# ST_LINK_V2.net
KiCad netlist of a schematic drawn in Altium Designer
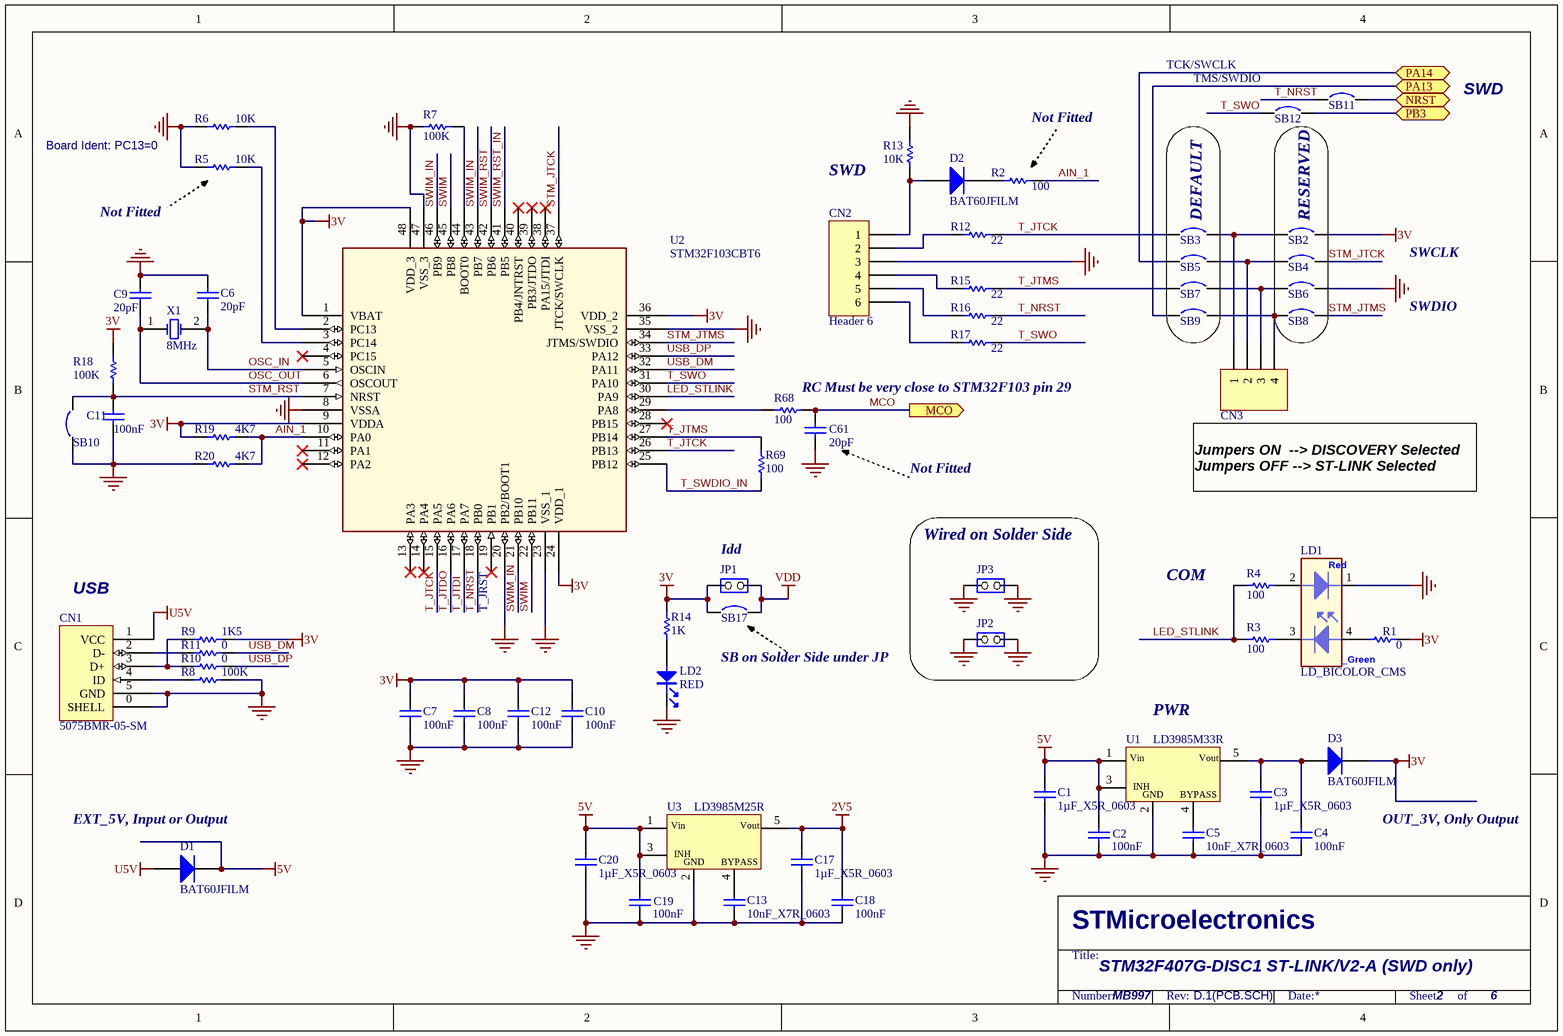
[diagram p0: ST_LINK_V2.SCHDOC]

(export (version "E")
  (design (tool "Eeschema 10.0.6"))
  (components
    (comp (ref "C1")
      (value "1µF_X5R_0603")
      (footprint "0603C")
      (description "0603  X5R 1µF")
      (fields (field (name "TOLERANCE") "10%"))
      (libsource (lib "MB963_1") (part "CAP SMD 0603  X5R 1µF 25V 10%"))
    )
    (comp (ref "C2")
      (value "100nF")
      (footprint "0603C")
      (description "Capacitor")
      (fields (field (name "PUBLISHER") "Altium Limited"))
      (libsource (lib "MB915_1") (part "Cap"))
    )
    (comp (ref "C3")
      (value "1µF_X5R_0603")
      (footprint "0603C")
      (description "0603  X5R 1µF")
      (fields (field (name "TOLERANCE") "10%"))
      (libsource (lib "MB963_1") (part "CAP SMD 0603  X5R 1µF 25V 10%"))
    )
    (comp (ref "C4")
      (value "100nF")
      (footprint "0603C")
      (description "Capacitor")
      (fields (field (name "PUBLISHER") "Altium Limited"))
      (libsource (lib "MB915_1") (part "Cap"))
    )
    (comp (ref "C5")
      (value "10nF_X7R_0603")
      (footprint "0603C")
      (description "0603  X7R 10NF")
      (fields (field (name "TOLERANCE") "10%"))
      (libsource (lib "MB963_1") (part "CAP SMD 0603  X7R 10000PF 50V 10%"))
    )
    (comp (ref "C6")
      (value "20pF")
      (footprint "0402C")
      (description "Capacitor")
      (fields (field (name "PUBLISHER") "Altium Limited"))
      (libsource (lib "MB915_1") (part "Cap"))
    )
    (comp (ref "C7")
      (value "100nF")
      (footprint "0402C")
      (description "Capacitor")
      (fields (field (name "PUBLISHER") "Altium Limited"))
      (libsource (lib "MB915_1") (part "Cap"))
    )
    (comp (ref "C8")
      (value "100nF")
      (footprint "0402C")
      (description "Capacitor")
      (fields (field (name "PUBLISHER") "Altium Limited"))
      (libsource (lib "MB915_1") (part "Cap"))
    )
    (comp (ref "C9")
      (value "20pF")
      (footprint "0402C")
      (description "Capacitor")
      (fields (field (name "PUBLISHER") "Altium Limited"))
      (libsource (lib "MB915_1") (part "Cap"))
    )
    (comp (ref "C10")
      (value "100nF")
      (footprint "0402C")
      (description "Capacitor")
      (fields (field (name "PUBLISHER") "Altium Limited"))
      (libsource (lib "MB915_1") (part "Cap"))
    )
    (comp (ref "C11")
      (value "100nF")
      (footprint "0402C")
      (description "Capacitor")
      (fields (field (name "PUBLISHER") "Altium Limited"))
      (libsource (lib "MB915_1") (part "Cap"))
    )
    (comp (ref "C12")
      (value "100nF")
      (footprint "0402C")
      (description "Capacitor")
      (fields (field (name "PUBLISHER") "Altium Limited"))
      (libsource (lib "MB915_1") (part "Cap"))
    )
    (comp (ref "C13")
      (value "10nF_X7R_0603")
      (footprint "0603C")
      (description "0603  X7R 10NF")
      (fields (field (name "TOLERANCE") "10%"))
      (libsource (lib "MB963_1") (part "CAP SMD 0603  X7R 10000PF 50V 10%"))
    )
    (comp (ref "C17")
      (value "1µF_X5R_0603")
      (footprint "0603C")
      (description "0603  X5R 1µF")
      (fields (field (name "TOLERANCE") "10%"))
      (libsource (lib "MB963_1") (part "CAP SMD 0603  X5R 1µF 25V 10%"))
    )
    (comp (ref "C18")
      (value "100nF")
      (footprint "0603C")
      (description "Capacitor")
      (fields (field (name "PUBLISHER") "Altium Limited"))
      (libsource (lib "MB915_1") (part "Cap"))
    )
    (comp (ref "C19")
      (value "100nF")
      (footprint "0603C")
      (description "Capacitor")
      (fields (field (name "PUBLISHER") "Altium Limited"))
      (libsource (lib "MB915_1") (part "Cap"))
    )
    (comp (ref "C20")
      (value "1µF_X5R_0603")
      (footprint "0603C")
      (description "0603  X5R 1µF")
      (fields (field (name "TOLERANCE") "10%"))
      (libsource (lib "MB963_1") (part "CAP SMD 0603  X5R 1µF 25V 10%"))
    )
    (comp (ref "C61")
      (value "20pF")
      (footprint "0402C")
      (description "Capacitor")
      (fields (field (name "PUBLISHER") "Altium Limited"))
      (libsource (lib "MB915_1") (part "Cap"))
    )
    (comp (ref "CN1")
      (value "5075BMR-05-SM")
      (footprint "USB-MINI-B-SMD")
      (libsource (lib "MB963") (part "USB-MINI-typeB connector"))
    )
    (comp (ref "CN2")
      (value "Header 6")
      (footprint "HDR1X6")
      (description "Header, 6-Pin")
      (fields (field (name "PUBLISHER") "Altium Limited"))
      (libsource (lib "Miscellaneous Connectors") (part "Header 6"))
    )
    (comp (ref "CN3")
      (value "Header 4")
      (footprint "Header 4")
      (description "Header, 4-Pin")
      (fields (field (name "PUBLISHER") "Altium Limited"))
      (libsource (lib "MB963_1") (part "Header 4"))
    )
    (comp (ref "D1")
      (value "BAT60JFILM")
      (footprint "SOD323/A")
      (fields (field (name "PUBLISHER") "Altium Limited"))
      (libsource (lib "MB997") (part "BAT60JFILM"))
    )
    (comp (ref "D2")
      (value "BAT60JFILM")
      (footprint "SOD323/A")
      (fields (field (name "PUBLISHER") "Altium Limited"))
      (libsource (lib "MB997") (part "BAT60JFILM"))
    )
    (comp (ref "D3")
      (value "BAT60JFILM")
      (footprint "SOD323/A")
      (fields (field (name "PUBLISHER") "Altium Limited"))
      (libsource (lib "MB997") (part "BAT60JFILM"))
    )
    (comp (ref "JP1") (value "~") (footprint "SIP2/2.54") (libsource (lib "*") (part "JP2")))
    (comp (ref "JP2") (value "~") (footprint "SIP2/2.54") (libsource (lib "*") (part "JP2")))
    (comp (ref "JP3") (value "~") (footprint "SIP2/2.54") (libsource (lib "*") (part "JP2")))
    (comp (ref "LD1")
      (value "LD_BICOLOR_CMS")
      (footprint "HSMF-A201")
      (description "Bicolor Led")
      (libsource (lib "MB963") (part "LD_BICOLOR_CMS"))
    )
    (comp (ref "LD2") (value "RED") (footprint "0603D") (libsource (lib "MB963_1") (part "PHOTO")))
    (comp (ref "R1")
      (value "0")
      (footprint "0402R")
      (description "Resistor")
      (fields (field (name "PUBLISHER") "Altium Limited"))
      (libsource (lib "MB915_1") (part "res1"))
    )
    (comp (ref "R2")
      (value "100")
      (footprint "0402R")
      (description "Resistor")
      (fields (field (name "PUBLISHER") "Altium Limited"))
      (libsource (lib "MB915_1") (part "res1"))
    )
    (comp (ref "R3")
      (value "100")
      (footprint "0402R")
      (description "Resistor")
      (fields (field (name "PUBLISHER") "Altium Limited"))
      (libsource (lib "MB915_1") (part "res1"))
    )
    (comp (ref "R4")
      (value "100")
      (footprint "0402R")
      (description "Resistor")
      (fields (field (name "PUBLISHER") "Altium Limited"))
      (libsource (lib "MB915_1") (part "res1"))
    )
    (comp (ref "R5")
      (value "10K")
      (footprint "0402R")
      (description "Resistor")
      (fields (field (name "PUBLISHER") "Altium Limited"))
      (libsource (lib "MB915_1") (part "res1"))
    )
    (comp (ref "R6")
      (value "10K")
      (footprint "0402R")
      (description "Resistor")
      (fields (field (name "PUBLISHER") "Altium Limited"))
      (libsource (lib "MB915_1") (part "res1"))
    )
    (comp (ref "R7")
      (value "100K")
      (footprint "0402R")
      (description "Resistor")
      (fields (field (name "PUBLISHER") "Altium Limited"))
      (libsource (lib "MB915_1") (part "res1"))
    )
    (comp (ref "R8")
      (value "100K")
      (footprint "0402R")
      (description "Resistor")
      (fields (field (name "PUBLISHER") "Altium Limited"))
      (libsource (lib "MB915_1") (part "res1"))
    )
    (comp (ref "R9")
      (value "1K5")
      (footprint "0402R")
      (description "Resistor")
      (fields (field (name "PUBLISHER") "Altium Limited"))
      (libsource (lib "MB915_1") (part "res1"))
    )
    (comp (ref "R10")
      (value "0")
      (footprint "0603R")
      (description "Resistor")
      (fields (field (name "PUBLISHER") "Altium Limited"))
      (libsource (lib "MB915_1") (part "res1"))
    )
    (comp (ref "R11")
      (value "0")
      (footprint "0603R")
      (description "Resistor")
      (fields (field (name "PUBLISHER") "Altium Limited"))
      (libsource (lib "MB915_1") (part "res1"))
    )
    (comp (ref "R12")
      (value "22")
      (footprint "0402R")
      (description "Resistor")
      (fields (field (name "PUBLISHER") "Altium Limited"))
      (libsource (lib "MB915_1") (part "res1"))
    )
    (comp (ref "R13")
      (value "10K")
      (footprint "0402R")
      (description "Resistor")
      (fields (field (name "PUBLISHER") "Altium Limited"))
      (libsource (lib "MB915_1") (part "res1"))
    )
    (comp (ref "R14")
      (value "1K")
      (footprint "0402R")
      (description "Resistor")
      (fields (field (name "PUBLISHER") "Altium Limited"))
      (libsource (lib "MB915_1") (part "res1"))
    )
    (comp (ref "R15")
      (value "22")
      (footprint "0402R")
      (description "Resistor")
      (fields (field (name "PUBLISHER") "Altium Limited"))
      (libsource (lib "MB915_1") (part "res1"))
    )
    (comp (ref "R16")
      (value "22")
      (footprint "0402R")
      (description "Resistor")
      (fields (field (name "PUBLISHER") "Altium Limited"))
      (libsource (lib "MB915_1") (part "res1"))
    )
    (comp (ref "R17")
      (value "22")
      (footprint "0402R")
      (description "Resistor")
      (fields (field (name "PUBLISHER") "Altium Limited"))
      (libsource (lib "MB915_1") (part "res1"))
    )
    (comp (ref "R18")
      (value "100K")
      (footprint "0402R")
      (description "Resistor")
      (fields (field (name "PUBLISHER") "Altium Limited"))
      (libsource (lib "MB915_1") (part "res1"))
    )
    (comp (ref "R19")
      (value "4K7")
      (footprint "0402R")
      (description "Resistor")
      (fields (field (name "PUBLISHER") "Altium Limited"))
      (libsource (lib "MB915_1") (part "res1"))
    )
    (comp (ref "R20")
      (value "4K7")
      (footprint "0402R")
      (description "Resistor")
      (fields (field (name "PUBLISHER") "Altium Limited"))
      (libsource (lib "MB915_1") (part "res1"))
    )
    (comp (ref "R68")
      (value "100")
      (footprint "0402R")
      (description "Resistor")
      (fields (field (name "PUBLISHER") "Altium Limited"))
      (libsource (lib "MB915_1") (part "res1"))
    )
    (comp (ref "R69")
      (value "100")
      (footprint "0402R")
      (description "Resistor")
      (fields (field (name "PUBLISHER") "Altium Limited"))
      (libsource (lib "MB915_1") (part "res1"))
    )
    (comp (ref "SB2")
      (value "Circuit Breaker")
      (footprint "JP2_SMD")
      (fields (field (name "PUBLISHER") "Altium Limited"))
      (libsource (lib "MB915") (part "Circuit Breaker"))
    )
    (comp (ref "SB3")
      (value "Circuit Breaker")
      (footprint "JP2_SMD")
      (fields (field (name "PUBLISHER") "Altium Limited"))
      (libsource (lib "MB915") (part "Circuit Breaker"))
    )
    (comp (ref "SB4")
      (value "Circuit Breaker")
      (footprint "JP2_SMD")
      (fields (field (name "PUBLISHER") "Altium Limited"))
      (libsource (lib "MB915") (part "Circuit Breaker"))
    )
    (comp (ref "SB5")
      (value "Circuit Breaker")
      (footprint "JP2_SMD")
      (fields (field (name "PUBLISHER") "Altium Limited"))
      (libsource (lib "MB915") (part "Circuit Breaker"))
    )
    (comp (ref "SB6")
      (value "Circuit Breaker")
      (footprint "JP2_SMD")
      (fields (field (name "PUBLISHER") "Altium Limited"))
      (libsource (lib "MB915") (part "Circuit Breaker"))
    )
    (comp (ref "SB7")
      (value "Circuit Breaker")
      (footprint "JP2_SMD")
      (fields (field (name "PUBLISHER") "Altium Limited"))
      (libsource (lib "MB915") (part "Circuit Breaker"))
    )
    (comp (ref "SB8")
      (value "Circuit Breaker")
      (footprint "JP2_SMD")
      (fields (field (name "PUBLISHER") "Altium Limited"))
      (libsource (lib "MB915") (part "Circuit Breaker"))
    )
    (comp (ref "SB9")
      (value "Circuit Breaker")
      (footprint "JP2_SMD")
      (fields (field (name "PUBLISHER") "Altium Limited"))
      (libsource (lib "MB915") (part "Circuit Breaker"))
    )
    (comp (ref "SB10")
      (value "Circuit Breaker")
      (footprint "JP2_SMD")
      (fields (field (name "PUBLISHER") "Altium Limited"))
      (libsource (lib "MB915") (part "Circuit Breaker"))
    )
    (comp (ref "SB11")
      (value "Circuit Breaker")
      (footprint "JP2_SMD")
      (fields (field (name "PUBLISHER") "Altium Limited"))
      (libsource (lib "MB915") (part "Circuit Breaker"))
    )
    (comp (ref "SB12")
      (value "Circuit Breaker")
      (footprint "JP2_SMD")
      (fields (field (name "PUBLISHER") "Altium Limited"))
      (libsource (lib "MB915") (part "Circuit Breaker"))
    )
    (comp (ref "SB17")
      (value "Circuit Breaker")
      (footprint "JP2_SMD")
      (fields (field (name "PUBLISHER") "Altium Limited"))
      (libsource (lib "MB915") (part "Circuit Breaker"))
    )
    (comp (ref "U1")
      (value "LD3985M33R")
      (footprint "SOT-23-5L")
      (description "Ultra low drop-low noise BiCMOS voltage, regulators low ESR capacitors compatible")
      (libsource (lib "MB997") (part "LD3985M33R"))
    )
    (comp (ref "U2")
      (value "STM32F103CBT6")
      (footprint "QFP48 7x7")
      (description "Medium-density performance line ARM-based 32-bit MCU with 128KB Flash")
      (libsource (lib "MCD_TOOLS") (part "STM32F103CBT6"))
    )
    (comp (ref "U3")
      (value "LD3985M25R")
      (footprint "SOT-23-5L")
      (description "Ultra low drop-low noise BiCMOS voltage, regulators low ESR capacitors compatible")
      (libsource (lib "MB997") (part "LD3985M25R"))
    )
    (comp (ref "X1")
      (value "8MHz")
      (footprint "XTAL1")
      (description "Crystal Oscillator")
      (fields (field (name "PUBLISHER") "Altium Limited"))
      (libsource (lib "MB963_1") (part "XTAL"))
    )
  )
  (nets
    (net (code "1") (name "/AIN_1") (class "Default")
      (node (ref "R19") (pin "2") (pinfunction "2_2") (pintype "passive"))
      (node (ref "R2") (pin "2") (pinfunction "2_2") (pintype "passive"))
      (node (ref "R20") (pin "2") (pinfunction "2_2") (pintype "passive"))
      (node (ref "U2") (pin "10") (pinfunction "PA0_10") (pintype "bidirectional"))
    )
    (net (code "2") (name "/LED_STLINK") (class "Default")
      (node (ref "R3") (pin "1") (pinfunction "1_1") (pintype "passive"))
      (node (ref "R4") (pin "1") (pinfunction "1_1") (pintype "passive"))
      (node (ref "U2") (pin "30") (pinfunction "PA9_30") (pintype "bidirectional"))
    )
    (net (code "3") (name "/MCO") (class "Default")
      (node (ref "C61") (pin "1") (pinfunction "1_1") (pintype "passive"))
      (node (ref "R68") (pin "2") (pinfunction "2_2") (pintype "passive"))
    )
    (net (code "4") (name "/NRST") (class "Default")
      (node (ref "SB11") (pin "2") (pinfunction "2_2") (pintype "passive"))
    )
    (net (code "5") (name "/OSC_IN") (class "Default")
      (node (ref "C6") (pin "2") (pinfunction "2_2") (pintype "passive"))
      (node (ref "U2") (pin "5") (pinfunction "OSCIN_5") (pintype "input"))
      (node (ref "X1") (pin "2") (pinfunction "OSC2_2") (pintype "passive"))
    )
    (net (code "6") (name "/OSC_OUT") (class "Default")
      (node (ref "C9") (pin "2") (pinfunction "2_2") (pintype "passive"))
      (node (ref "U2") (pin "6") (pinfunction "OSCOUT_6") (pintype "output"))
      (node (ref "X1") (pin "1") (pinfunction "OSC1_1") (pintype "passive"))
    )
    (net (code "7") (name "/PA13") (class "Default")
      (node (ref "SB9") (pin "1") (pinfunction "1_1") (pintype "passive"))
    )
    (net (code "8") (name "/PA14") (class "Default")
      (node (ref "SB5") (pin "1") (pinfunction "1_1") (pintype "passive"))
    )
    (net (code "9") (name "/PB3") (class "Default")
      (node (ref "SB12") (pin "2") (pinfunction "2_2") (pintype "passive"))
    )
    (net (code "10") (name "/STM_JTCK") (class "Default")
      (node (ref "SB4") (pin "2") (pinfunction "2_2") (pintype "passive"))
      (node (ref "U2") (pin "37") (pinfunction "JTCK/SWCLK_37") (pintype "bidirectional"))
    )
    (net (code "11") (name "/STM_JTMS") (class "Default")
      (node (ref "SB8") (pin "2") (pinfunction "2_2") (pintype "passive"))
      (node (ref "U2") (pin "34") (pinfunction "JTMS/SWDIO_34") (pintype "bidirectional"))
    )
    (net (code "12") (name "/STM_RST") (class "Default")
      (node (ref "C11") (pin "2") (pinfunction "2_2") (pintype "passive"))
      (node (ref "R18") (pin "1") (pinfunction "1_1") (pintype "passive"))
      (node (ref "SB10") (pin "2") (pinfunction "2_2") (pintype "passive"))
      (node (ref "U2") (pin "7") (pinfunction "NRST_7") (pintype "input"))
    )
    (net (code "13") (name "/SWIM") (class "Default")
      (node (ref "U2") (pin "22") (pinfunction "PB11_22") (pintype "bidirectional"))
      (node (ref "U2") (pin "45") (pinfunction "PB8_45") (pintype "bidirectional"))
    )
    (net (code "14") (name "/SWIM_IN") (class "Default")
      (node (ref "U2") (pin "21") (pinfunction "PB10_21") (pintype "bidirectional"))
      (node (ref "U2") (pin "43") (pinfunction "PB7_43") (pintype "bidirectional"))
      (node (ref "U2") (pin "46") (pinfunction "PB9_46") (pintype "bidirectional"))
    )
    (net (code "15") (name "/SWIM_RST") (class "Default")
      (node (ref "U2") (pin "42") (pinfunction "PB6_42") (pintype "bidirectional"))
    )
    (net (code "16") (name "/SWIM_RST_IN") (class "Default")
      (node (ref "U2") (pin "41") (pinfunction "PB5_41") (pintype "bidirectional"))
    )
    (net (code "17") (name "/T_JTCK") (class "Default")
      (node (ref "R12") (pin "2") (pinfunction "2_2") (pintype "passive"))
      (node (ref "SB3") (pin "1") (pinfunction "1_1") (pintype "passive"))
      (node (ref "U2") (pin "15") (pinfunction "PA5_15") (pintype "bidirectional"))
      (node (ref "U2") (pin "26") (pinfunction "PB13_26") (pintype "bidirectional"))
    )
    (net (code "18") (name "/T_JTDI") (class "Default")
      (node (ref "U2") (pin "17") (pinfunction "PA7_17") (pintype "bidirectional"))
    )
    (net (code "19") (name "/T_JTDO") (class "Default")
      (node (ref "U2") (pin "16") (pinfunction "PA6_16") (pintype "bidirectional"))
    )
    (net (code "20") (name "/T_JTMS") (class "Default")
      (node (ref "R15") (pin "2") (pinfunction "2_2") (pintype "passive"))
      (node (ref "R69") (pin "2") (pinfunction "2_2") (pintype "passive"))
      (node (ref "SB7") (pin "1") (pinfunction "1_1") (pintype "passive"))
      (node (ref "U2") (pin "27") (pinfunction "PB14_27") (pintype "bidirectional"))
    )
    (net (code "21") (name "/T_NRST") (class "Default")
      (node (ref "R16") (pin "2") (pinfunction "2_2") (pintype "passive"))
      (node (ref "SB11") (pin "1") (pinfunction "1_1") (pintype "passive"))
      (node (ref "U2") (pin "18") (pinfunction "PB0_18") (pintype "bidirectional"))
    )
    (net (code "22") (name "/T_SWDIO_IN") (class "Default")
      (node (ref "R69") (pin "1") (pinfunction "1_1") (pintype "passive"))
      (node (ref "U2") (pin "25") (pinfunction "PB12_25") (pintype "bidirectional"))
    )
    (net (code "23") (name "/T_SWO") (class "Default")
      (node (ref "R17") (pin "2") (pinfunction "2_2") (pintype "passive"))
      (node (ref "SB12") (pin "1") (pinfunction "1_1") (pintype "passive"))
      (node (ref "U2") (pin "31") (pinfunction "PA10_31") (pintype "bidirectional"))
    )
    (net (code "24") (name "/USB_DM") (class "Default")
      (node (ref "R11") (pin "2") (pinfunction "2_2") (pintype "passive"))
      (node (ref "U2") (pin "32") (pinfunction "PA11_32") (pintype "bidirectional"))
    )
    (net (code "25") (name "/USB_DP") (class "Default")
      (node (ref "R10") (pin "2") (pinfunction "2_2") (pintype "passive"))
      (node (ref "U2") (pin "33") (pinfunction "PA12_33") (pintype "bidirectional"))
    )
    (net (code "26") (name "2V5") (class "Default")
      (node (ref "C17") (pin "1") (pinfunction "1_1") (pintype "passive"))
      (node (ref "C18") (pin "2") (pinfunction "2_2") (pintype "passive"))
      (node (ref "U3") (pin "5") (pinfunction "Vout_5") (pintype "passive"))
    )
    (net (code "27") (name "3V") (class "Default")
      (node (ref "C10") (pin "2") (pinfunction "2_2") (pintype "passive"))
      (node (ref "C12") (pin "1") (pinfunction "1_1") (pintype "passive"))
      (node (ref "C7") (pin "2") (pinfunction "2_2") (pintype "passive"))
      (node (ref "C8") (pin "2") (pinfunction "2_2") (pintype "passive"))
      (node (ref "D3") (pin "2") (pinfunction "K_2") (pintype "passive"))
      (node (ref "JP1") (pin "1") (pinfunction "COMMON_1") (pintype "passive"))
      (node (ref "R1") (pin "2") (pinfunction "2_2") (pintype "passive"))
      (node (ref "R14") (pin "2") (pinfunction "2_2") (pintype "passive"))
      (node (ref "R18") (pin "2") (pinfunction "2_2") (pintype "passive"))
      (node (ref "R19") (pin "1") (pinfunction "1_1") (pintype "passive"))
      (node (ref "R9") (pin "2") (pinfunction "2_2") (pintype "passive"))
      (node (ref "SB17") (pin "1") (pinfunction "1_1") (pintype "passive"))
      (node (ref "SB2") (pin "2") (pinfunction "2_2") (pintype "passive"))
      (node (ref "U2") (pin "1") (pinfunction "VBAT_1") (pintype "power_in"))
      (node (ref "U2") (pin "24") (pinfunction "VDD_1_24") (pintype "power_in"))
      (node (ref "U2") (pin "36") (pinfunction "VDD_2_36") (pintype "power_in"))
      (node (ref "U2") (pin "48") (pinfunction "VDD_3_48") (pintype "power_in"))
      (node (ref "U2") (pin "9") (pinfunction "VDDA_9") (pintype "power_in"))
    )
    (net (code "28") (name "5V") (class "Default")
      (node (ref "C1") (pin "2") (pinfunction "2_2") (pintype "passive"))
      (node (ref "C19") (pin "2") (pinfunction "2_2") (pintype "passive"))
      (node (ref "C2") (pin "2") (pinfunction "2_2") (pintype "passive"))
      (node (ref "C20") (pin "2") (pinfunction "2_2") (pintype "passive"))
      (node (ref "D1") (pin "2") (pinfunction "K_2") (pintype "passive"))
      (node (ref "U1") (pin "1") (pinfunction "Vin_1") (pintype "passive"))
      (node (ref "U1") (pin "3") (pinfunction "CE_3") (pintype "passive"))
      (node (ref "U3") (pin "1") (pinfunction "Vin_1") (pintype "passive"))
      (node (ref "U3") (pin "3") (pinfunction "CE_3") (pintype "passive"))
    )
    (net (code "29") (name "GND") (class "Default")
      (node (ref "C1") (pin "1") (pinfunction "1_1") (pintype "passive"))
      (node (ref "C10") (pin "1") (pinfunction "1_1") (pintype "passive"))
      (node (ref "C11") (pin "1") (pinfunction "1_1") (pintype "passive"))
      (node (ref "C12") (pin "2") (pinfunction "2_2") (pintype "passive"))
      (node (ref "C13") (pin "1") (pinfunction "1_1") (pintype "passive"))
      (node (ref "C17") (pin "2") (pinfunction "2_2") (pintype "passive"))
      (node (ref "C18") (pin "1") (pinfunction "1_1") (pintype "passive"))
      (node (ref "C19") (pin "1") (pinfunction "1_1") (pintype "passive"))
      (node (ref "C2") (pin "1") (pinfunction "1_1") (pintype "passive"))
      (node (ref "C20") (pin "1") (pinfunction "1_1") (pintype "passive"))
      (node (ref "C3") (pin "2") (pinfunction "2_2") (pintype "passive"))
      (node (ref "C4") (pin "1") (pinfunction "1_1") (pintype "passive"))
      (node (ref "C5") (pin "1") (pinfunction "1_1") (pintype "passive"))
      (node (ref "C6") (pin "1") (pinfunction "1_1") (pintype "passive"))
      (node (ref "C61") (pin "2") (pinfunction "2_2") (pintype "passive"))
      (node (ref "C7") (pin "1") (pinfunction "1_1") (pintype "passive"))
      (node (ref "C8") (pin "1") (pinfunction "1_1") (pintype "passive"))
      (node (ref "C9") (pin "1") (pinfunction "1_1") (pintype "passive"))
      (node (ref "CN1") (pin "0") (pinfunction "SHELL_0") (pintype "power_in"))
      (node (ref "CN1") (pin "5") (pinfunction "GND_5") (pintype "power_in"))
      (node (ref "CN2") (pin "3") (pinfunction "3_3") (pintype "passive"))
      (node (ref "JP2") (pin "1") (pinfunction "COMMON_1") (pintype "passive"))
      (node (ref "JP2") (pin "2") (pinfunction "NO_2") (pintype "passive"))
      (node (ref "JP3") (pin "1") (pinfunction "COMMON_1") (pintype "passive"))
      (node (ref "JP3") (pin "2") (pinfunction "NO_2") (pintype "passive"))
      (node (ref "LD1") (pin "1") (pinfunction "1_1") (pintype "passive"))
      (node (ref "LD2") (pin "2") (pintype "passive"))
      (node (ref "R13") (pin "2") (pinfunction "2_2") (pintype "passive"))
      (node (ref "R20") (pin "1") (pinfunction "1_1") (pintype "passive"))
      (node (ref "R5") (pin "1") (pinfunction "1_1") (pintype "passive"))
      (node (ref "R6") (pin "1") (pinfunction "1_1") (pintype "passive"))
      (node (ref "R7") (pin "1") (pinfunction "1_1") (pintype "passive"))
      (node (ref "R8") (pin "2") (pinfunction "2_2") (pintype "passive"))
      (node (ref "SB10") (pin "1") (pinfunction "1_1") (pintype "passive"))
      (node (ref "SB6") (pin "2") (pinfunction "2_2") (pintype "passive"))
      (node (ref "U1") (pin "2") (pinfunction "GND_2") (pintype "passive"))
      (node (ref "U2") (pin "20") (pinfunction "PB2/BOOT1_20") (pintype "bidirectional"))
      (node (ref "U2") (pin "23") (pinfunction "VSS_1_23") (pintype "power_in"))
      (node (ref "U2") (pin "35") (pinfunction "VSS_2_35") (pintype "power_in"))
      (node (ref "U2") (pin "47") (pinfunction "VSS_3_47") (pintype "power_in"))
      (node (ref "U2") (pin "8") (pinfunction "VSSA_8") (pintype "power_in"))
      (node (ref "U3") (pin "2") (pinfunction "GND_2") (pintype "passive"))
    )
    (net (code "30") (name "Net-(CN1-D+)") (class "Default")
      (node (ref "CN1") (pin "3") (pinfunction "D+_3") (pintype "bidirectional"))
      (node (ref "R10") (pin "1") (pinfunction "1_1") (pintype "passive"))
      (node (ref "R9") (pin "1") (pinfunction "1_1") (pintype "passive"))
    )
    (net (code "31") (name "Net-(CN1-D-)") (class "Default")
      (node (ref "CN1") (pin "2") (pinfunction "D-_2") (pintype "bidirectional"))
      (node (ref "R11") (pin "1") (pinfunction "1_1") (pintype "passive"))
    )
    (net (code "32") (name "Net-(CN1-ID)") (class "Default")
      (node (ref "CN1") (pin "4") (pinfunction "ID_4") (pintype "input"))
      (node (ref "R8") (pin "1") (pinfunction "1_1") (pintype "passive"))
    )
    (net (code "33") (name "Net-(CN2-Pad2)") (class "Default")
      (node (ref "CN2") (pin "2") (pinfunction "2_2") (pintype "passive"))
      (node (ref "R12") (pin "1") (pinfunction "1_1") (pintype "passive"))
    )
    (net (code "34") (name "Net-(CN2-Pad4)") (class "Default")
      (node (ref "CN2") (pin "4") (pinfunction "4_4") (pintype "passive"))
      (node (ref "R15") (pin "1") (pinfunction "1_1") (pintype "passive"))
    )
    (net (code "35") (name "Net-(CN2-Pad5)") (class "Default")
      (node (ref "CN2") (pin "5") (pinfunction "5_5") (pintype "passive"))
      (node (ref "R16") (pin "1") (pinfunction "1_1") (pintype "passive"))
    )
    (net (code "36") (name "Net-(CN2-Pad6)") (class "Default")
      (node (ref "CN2") (pin "6") (pinfunction "6_6") (pintype "passive"))
      (node (ref "R17") (pin "1") (pinfunction "1_1") (pintype "passive"))
    )
    (net (code "37") (name "Net-(CN3-Pad1)") (class "Default")
      (node (ref "CN3") (pin "1") (pinfunction "1_1") (pintype "passive"))
      (node (ref "SB2") (pin "1") (pinfunction "1_1") (pintype "passive"))
      (node (ref "SB3") (pin "2") (pinfunction "2_2") (pintype "passive"))
    )
    (net (code "38") (name "Net-(CN3-Pad2)") (class "Default")
      (node (ref "CN3") (pin "2") (pinfunction "2_2") (pintype "passive"))
      (node (ref "SB4") (pin "1") (pinfunction "1_1") (pintype "passive"))
      (node (ref "SB5") (pin "2") (pinfunction "2_2") (pintype "passive"))
    )
    (net (code "39") (name "Net-(CN3-Pad3)") (class "Default")
      (node (ref "CN3") (pin "3") (pinfunction "3_3") (pintype "passive"))
      (node (ref "SB6") (pin "1") (pinfunction "1_1") (pintype "passive"))
      (node (ref "SB7") (pin "2") (pinfunction "2_2") (pintype "passive"))
    )
    (net (code "40") (name "Net-(CN3-Pad4)") (class "Default")
      (node (ref "CN3") (pin "4") (pinfunction "4_4") (pintype "passive"))
      (node (ref "SB8") (pin "1") (pinfunction "1_1") (pintype "passive"))
      (node (ref "SB9") (pin "2") (pinfunction "2_2") (pintype "passive"))
    )
    (net (code "41") (name "Net-(D2-A)") (class "Default")
      (node (ref "CN2") (pin "1") (pinfunction "1_1") (pintype "passive"))
      (node (ref "D2") (pin "1") (pinfunction "A_1") (pintype "passive"))
      (node (ref "R13") (pin "1") (pinfunction "1_1") (pintype "passive"))
    )
    (net (code "42") (name "Net-(D2-K)") (class "Default")
      (node (ref "D2") (pin "2") (pinfunction "K_2") (pintype "passive"))
      (node (ref "R2") (pin "1") (pinfunction "1_1") (pintype "passive"))
    )
    (net (code "43") (name "Net-(D3-A)") (class "Default")
      (node (ref "C3") (pin "1") (pinfunction "1_1") (pintype "passive"))
      (node (ref "C4") (pin "2") (pinfunction "2_2") (pintype "passive"))
      (node (ref "D3") (pin "1") (pinfunction "A_1") (pintype "passive"))
      (node (ref "U1") (pin "5") (pinfunction "Vout_5") (pintype "passive"))
    )
    (net (code "44") (name "Net-(LD1-Pad2)") (class "Default")
      (node (ref "LD1") (pin "2") (pinfunction "2_2") (pintype "passive"))
      (node (ref "R4") (pin "2") (pinfunction "2_2") (pintype "passive"))
    )
    (net (code "45") (name "Net-(LD1-Pad3)") (class "Default")
      (node (ref "LD1") (pin "3") (pinfunction "3_3") (pintype "passive"))
      (node (ref "R3") (pin "2") (pinfunction "2_2") (pintype "passive"))
    )
    (net (code "46") (name "Net-(LD1-Pad4)") (class "Default")
      (node (ref "LD1") (pin "4") (pinfunction "4_4") (pintype "passive"))
      (node (ref "R1") (pin "1") (pinfunction "1_1") (pintype "passive"))
    )
    (net (code "47") (name "Net-(LD2-Pad1)") (class "Default")
      (node (ref "LD2") (pin "1") (pintype "passive"))
      (node (ref "R14") (pin "1") (pinfunction "1_1") (pintype "passive"))
    )
    (net (code "48") (name "Net-(U1-BYPASS)") (class "Default")
      (node (ref "C5") (pin "2") (pinfunction "2_2") (pintype "passive"))
      (node (ref "U1") (pin "4") (pinfunction "BYPASS_4") (pintype "passive"))
    )
    (net (code "49") (name "Net-(U2-BOOT0)") (class "Default")
      (node (ref "R7") (pin "2") (pinfunction "2_2") (pintype "passive"))
      (node (ref "U2") (pin "44") (pinfunction "BOOT0_44") (pintype "bidirectional"))
    )
    (net (code "50") (name "Net-(U2-PA8)") (class "Default")
      (node (ref "R68") (pin "1") (pinfunction "1_1") (pintype "passive"))
      (node (ref "U2") (pin "29") (pinfunction "PA8_29") (pintype "bidirectional"))
    )
    (net (code "51") (name "Net-(U2-PC13)") (class "Default")
      (node (ref "R6") (pin "2") (pinfunction "2_2") (pintype "passive"))
      (node (ref "U2") (pin "2") (pinfunction "PC13_2") (pintype "bidirectional"))
    )
    (net (code "52") (name "Net-(U2-PC14)") (class "Default")
      (node (ref "R5") (pin "2") (pinfunction "2_2") (pintype "passive"))
      (node (ref "U2") (pin "3") (pinfunction "PC14_3") (pintype "bidirectional"))
    )
    (net (code "53") (name "Net-(U3-BYPASS)") (class "Default")
      (node (ref "C13") (pin "2") (pinfunction "2_2") (pintype "passive"))
      (node (ref "U3") (pin "4") (pinfunction "BYPASS_4") (pintype "passive"))
    )
    (net (code "54") (name "U5V") (class "Default")
      (node (ref "CN1") (pin "1") (pinfunction "VCC_1") (pintype "power_in"))
      (node (ref "D1") (pin "1") (pinfunction "A_1") (pintype "passive"))
    )
    (net (code "55") (name "VDD") (class "Default")
      (node (ref "JP1") (pin "2") (pinfunction "NO_2") (pintype "passive"))
      (node (ref "SB17") (pin "2") (pinfunction "2_2") (pintype "passive"))
    )
    (net (code "56") (name "unconnected-(U2-PA1-Pad11)") (class "Default")
      (node (ref "U2") (pin "11") (pinfunction "PA1_11") (pintype "bidirectional+no_connect"))
    )
    (net (code "57") (name "unconnected-(U2-PA2-Pad12)") (class "Default")
      (node (ref "U2") (pin "12") (pinfunction "PA2_12") (pintype "bidirectional+no_connect"))
    )
    (net (code "58") (name "unconnected-(U2-PA3-Pad13)") (class "Default")
      (node (ref "U2") (pin "13") (pinfunction "PA3_13") (pintype "bidirectional+no_connect"))
    )
    (net (code "59") (name "unconnected-(U2-PA4-Pad14)") (class "Default")
      (node (ref "U2") (pin "14") (pinfunction "PA4_14") (pintype "bidirectional+no_connect"))
    )
    (net (code "60") (name "unconnected-(U2-PA15{slash}JTDI-Pad38)") (class "Default")
      (node (ref "U2") (pin "38") (pinfunction "PA15/JTDI_38") (pintype "bidirectional+no_connect"))
    )
    (net (code "61") (name "unconnected-(U2-PB1-Pad19)") (class "Default")
      (node (ref "U2") (pin "19") (pinfunction "PB1_19") (pintype "input+no_connect"))
    )
    (net (code "62") (name "unconnected-(U2-PB3{slash}JTDO-Pad39)") (class "Default")
      (node (ref "U2") (pin "39") (pinfunction "PB3/JTDO_39") (pintype "bidirectional+no_connect"))
    )
    (net (code "63") (name "unconnected-(U2-PB4{slash}JNTRST-Pad40)") (class "Default")
      (node (ref "U2") (pin "40") (pinfunction "PB4/JNTRST_40") (pintype "bidirectional+no_connect"))
    )
    (net (code "64") (name "unconnected-(U2-PB15-Pad28)") (class "Default")
      (node (ref "U2") (pin "28") (pinfunction "PB15_28") (pintype "bidirectional+no_connect"))
    )
    (net (code "65") (name "unconnected-(U2-PC15-Pad4)") (class "Default")
      (node (ref "U2") (pin "4") (pinfunction "PC15_4") (pintype "bidirectional+no_connect"))
    )
  )
)
